# Buck.net
KiCad netlist of a schematic drawn in Altium Designer
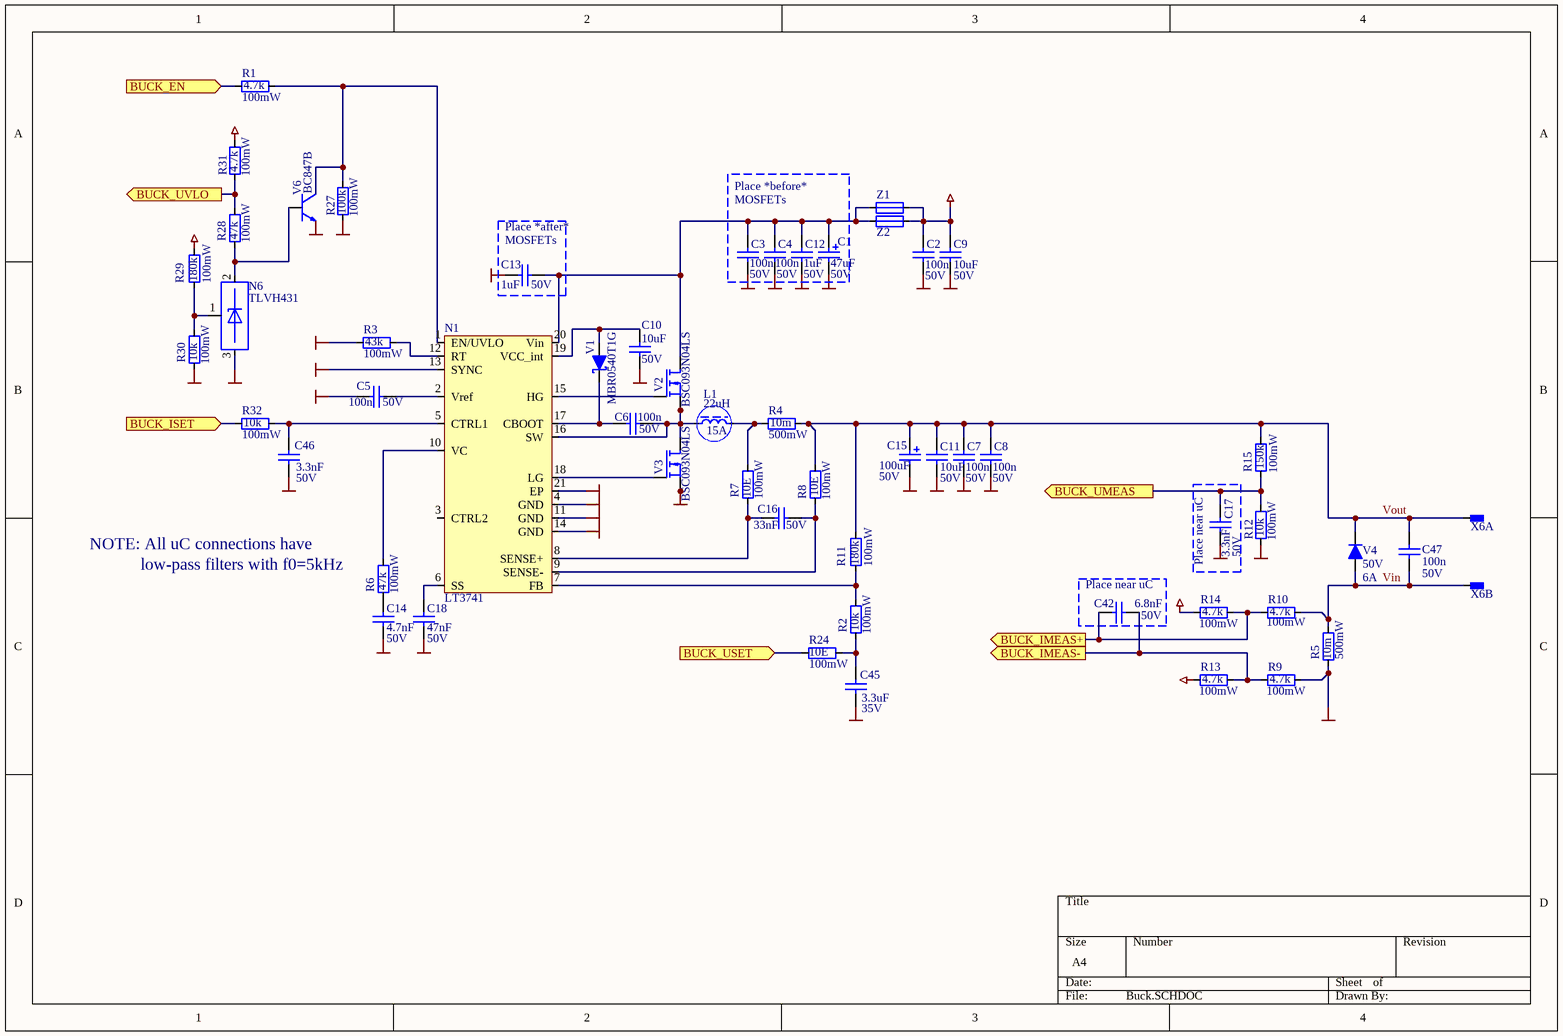
[diagram p0: Buck.SCHDOC]

(export (version "E")
  (design (tool "Eeschema 10.0.6"))
  (components
    (comp (ref "C1")
      (value "C_SMD_ALU_47U_50V_20%_PCV1H470MCL7GS")
      (footprint "SMD_CAP_CV_8x10L")
      (fields (field (name "ALTIUM_VALUE") "47uF") (field (name "VALUE2") "50V"))
      (libsource (lib "C-Capacitor") (part "C_SMD_ALU_47U_50V_20%_PCV1H470MCL7GS"))
    )
    (comp (ref "C2")
      (value "C_SMD_CER_100N_50V_10%_X7R_0603")
      (footprint "SMD_0603")
      (description "SMD Capacitor")
      (fields (field (name "ALTIUM_VALUE") "100n") (field (name "VALUE2") "50V"))
      (libsource (lib "C-Capacitor") (part "C_SMD_CER_100N_50V_10%_X7R_0603"))
    )
    (comp (ref "C3")
      (value "C_SMD_CER_100N_50V_10%_X7R_0603")
      (footprint "SMD_0603")
      (description "SMD Capacitor")
      (fields (field (name "ALTIUM_VALUE") "100n") (field (name "VALUE2") "50V"))
      (libsource (lib "C-Capacitor") (part "C_SMD_CER_100N_50V_10%_X7R_0603"))
    )
    (comp (ref "C4")
      (value "C_SMD_CER_100N_50V_10%_X7R_0603")
      (footprint "SMD_0603")
      (description "SMD Capacitor")
      (fields (field (name "ALTIUM_VALUE") "100n") (field (name "VALUE2") "50V"))
      (libsource (lib "C-Capacitor") (part "C_SMD_CER_100N_50V_10%_X7R_0603"))
    )
    (comp (ref "C5")
      (value "C_SMD_CER_100N_50V_10%_X7R_0603")
      (footprint "SMD_0603")
      (description "SMD Capacitor")
      (fields (field (name "ALTIUM_VALUE") "100n") (field (name "VALUE2") "50V"))
      (libsource (lib "C-Capacitor") (part "C_SMD_CER_100N_50V_10%_X7R_0603"))
    )
    (comp (ref "C6")
      (value "C_SMD_CER_100N_50V_10%_X7R_0603")
      (footprint "SMD_0603")
      (description "SMD Capacitor")
      (fields (field (name "ALTIUM_VALUE") "100n") (field (name "VALUE2") "50V"))
      (libsource (lib "C-Capacitor") (part "C_SMD_CER_100N_50V_10%_X7R_0603"))
    )
    (comp (ref "C7")
      (value "C_SMD_CER_100N_50V_10%_X7R_0603")
      (footprint "SMD_0603")
      (description "SMD Capacitor")
      (fields (field (name "ALTIUM_VALUE") "100n") (field (name "VALUE2") "50V"))
      (libsource (lib "C-Capacitor") (part "C_SMD_CER_100N_50V_10%_X7R_0603"))
    )
    (comp (ref "C8")
      (value "C_SMD_CER_100N_50V_10%_X7R_0603")
      (footprint "SMD_0603")
      (description "SMD Capacitor")
      (fields (field (name "ALTIUM_VALUE") "100n") (field (name "VALUE2") "50V"))
      (libsource (lib "C-Capacitor") (part "C_SMD_CER_100N_50V_10%_X7R_0603"))
    )
    (comp (ref "C9")
      (value "C_SMD_CER_10U_50V_10%_X7R_1210")
      (footprint "SMD_1210")
      (description "SMD Ceramic capacitor")
      (fields (field (name "ALTIUM_VALUE") "10uF") (field (name "VALUE2") "50V"))
      (libsource (lib "AM") (part "C_SMD_CER_10U_50V_10%_X7R_1210"))
    )
    (comp (ref "C10")
      (value "C_SMD_CER_10U_50V_10%_X7R_1210")
      (footprint "SMD_1210")
      (description "SMD Ceramic capacitor")
      (fields (field (name "ALTIUM_VALUE") "10uF") (field (name "VALUE2") "50V"))
      (libsource (lib "AM") (part "C_SMD_CER_10U_50V_10%_X7R_1210"))
    )
    (comp (ref "C11")
      (value "C_SMD_CER_10U_50V_10%_X7R_1210")
      (footprint "SMD_1210")
      (description "SMD Ceramic capacitor")
      (fields (field (name "ALTIUM_VALUE") "10uF") (field (name "VALUE2") "50V"))
      (libsource (lib "AM") (part "C_SMD_CER_10U_50V_10%_X7R_1210"))
    )
    (comp (ref "C12")
      (value "C_SMD_CER_1U_50V_10%_X7R_0805")
      (footprint "SMD_0805")
      (fields (field (name "ALTIUM_VALUE") "1uF") (field (name "VALUE2") "50V"))
      (libsource (lib "AM") (part "C_SMD_CER_1U_50V_10%_X7R_0805"))
    )
    (comp (ref "C13")
      (value "C_SMD_CER_1U_50V_10%_X7R_0805")
      (footprint "SMD_0805")
      (fields (field (name "ALTIUM_VALUE") "1uF") (field (name "VALUE2") "50V"))
      (libsource (lib "AM") (part "C_SMD_CER_1U_50V_10%_X7R_0805"))
    )
    (comp (ref "C14")
      (value "C_SMD_CER_4N7_50V_10%_X7R_0603")
      (footprint "SMD_0603")
      (description "SMD Capacitor ceramic")
      (fields (field (name "ALTIUM_VALUE") "4.7nF") (field (name "VALUE2") "50V"))
      (libsource (lib "C-Capacitor") (part "C_SMD_CER_4N7_50V_10%_X7R_0603"))
    )
    (comp (ref "C15")
      (value "C_SMD_ALU_100U_50V_20%_PCV1H101MCL2GS")
      (footprint "SMD_CAP_CV_10x12.7L")
      (fields (field (name "ALTIUM_VALUE") "100uF") (field (name "VALUE2") "50V"))
      (libsource (lib "AM") (part "C_SMD_ALU_100U_50V_20%_PCV1H101MCL2GS"))
    )
    (comp (ref "C16")
      (value "C_SMD_CER_33N_50V_10%_X7R_0603")
      (footprint "SMD_0603")
      (fields (field (name "ALTIUM_VALUE") "33nF") (field (name "VALUE2") "50V"))
      (libsource (lib "AM") (part "C_SMD_CER_33N_50V_10%_X7R_0603"))
    )
    (comp (ref "C17")
      (value "C_SMD_CER_3N3_50V_10%_X7R_0603")
      (footprint "SMD_0603")
      (description "Thinfilm Ceramic Capacitor")
      (fields (field (name "ALTIUM_VALUE") "3.3nF") (field (name "VALUE2") "50V"))
      (libsource (lib "AM") (part "C_SMD_CER_3N3_50V_10%_X7R_0603"))
    )
    (comp (ref "C18")
      (value "C_SMD_CER_47N_50V_10%_X7R_0603")
      (footprint "SMD_0603")
      (description "SMD capacitor")
      (fields (field (name "ALTIUM_VALUE") "47nF") (field (name "VALUE2") "50V"))
      (libsource (lib "C-Capacitor") (part "C_SMD_CER_47N_50V_10%_X7R_0603"))
    )
    (comp (ref "C42")
      (value "C_SMD_CER_6N8_50V_10%_X7R_0603")
      (footprint "SMD_0603")
      (fields (field (name "ALTIUM_VALUE") "6.8nF") (field (name "VALUE2") "50V"))
      (libsource (lib "AM") (part "C_SMD_CER_6N8_50V_10%_X7R_0603"))
    )
    (comp (ref "C45")
      (value "C_SMD_CER_3U3_35V_10%_X7R_0805")
      (footprint "SMD_0805")
      (fields (field (name "ALTIUM_VALUE") "3.3uF") (field (name "VALUE2") "35V"))
      (libsource (lib "AM") (part "C_SMD_CER_3U3_35V_10%_X7R_0805"))
    )
    (comp (ref "C46")
      (value "C_SMD_CER_3N3_50V_10%_X7R_0603")
      (footprint "SMD_0603")
      (description "Thinfilm Ceramic Capacitor")
      (fields (field (name "ALTIUM_VALUE") "3.3nF") (field (name "VALUE2") "50V"))
      (libsource (lib "AM") (part "C_SMD_CER_3N3_50V_10%_X7R_0603"))
    )
    (comp (ref "C47")
      (value "C_SMD_CER_100N_50V_10%_X7R_0603")
      (footprint "SMD_0603")
      (description "SMD Capacitor")
      (fields (field (name "ALTIUM_VALUE") "100n") (field (name "VALUE2") "50V"))
      (libsource (lib "C-Capacitor") (part "C_SMD_CER_100N_50V_10%_X7R_0603"))
    )
    (comp (ref "L1")
      (value "L_SMD_22U_15A_7MOHM_20%_74435582200")
      (footprint "SMD_INDUCT-74435582200")
      (fields (field (name "ALTIUM_VALUE") "22uH") (field (name "VALUE2") "15A"))
      (libsource (lib "AM") (part "L_SMD_22U_15A_7MOHM_20%_74435582200"))
    )
    (comp (ref "N1")
      (value "N_LT3741EUF_QFN-20")
      (footprint "SMD_QFN-20")
      (description "High Power, CCVC, Step-Down Controller")
      (fields (field (name "TYPE") "LT3741"))
      (libsource (lib "N-Analog") (part "N_LT3741EUF_QFN-20"))
    )
    (comp (ref "N6")
      (value "N_TLVH431_SOT23-3")
      (footprint "SMD_SOT_23_3")
      (description "LOW-VOLTAGE ADJUSTABLE PRECISION SHUNT REGULATORS")
      (fields (field (name "TYPE") "TLVH431"))
      (libsource (lib "AM") (part "N_TLVH431_SOT23-3"))
    )
    (comp (ref "R1")
      (value "R_SMD_THINFILM_4K7_0W1_1%_50PPM_0603")
      (footprint "SMD_0603")
      (description "SMD Resistor")
      (fields (field (name "ALTIUM_VALUE") "4.7k") (field (name "VALUE2") "100mW"))
      (libsource (lib "R-Resistor") (part "R_SMD_THINFILM_4K7_0W1_1%_50PPM_0603"))
    )
    (comp (ref "R2")
      (value "R_SMD_THINFILM_10K_0W1_1%_50PPM_0603")
      (footprint "SMD_0603")
      (description "SMD Resistor")
      (fields (field (name "ALTIUM_VALUE") "10k") (field (name "VALUE2") "100mW"))
      (libsource (lib "R-Resistor") (part "R_SMD_THINFILM_10K_0W1_1%_50PPM_0603"))
    )
    (comp (ref "R3")
      (value "R_SMD_THINFILM_43K_0W1_0.1%_25PPM_0603")
      (footprint "SMD_0603")
      (description "SMD Resistor")
      (fields (field (name "ALTIUM_VALUE") "43k") (field (name "VALUE2") "100mW"))
      (libsource (lib "AM") (part "R_SMD_THINFILM_43K_0W1_0.1%_25PPM_0603"))
    )
    (comp (ref "R4")
      (value "R_SMD_THICKFILM_0E01_0W5_0.5%_50PPM_1206")
      (footprint "SMD_1206")
      (description "SMD Current sense resistor")
      (fields (field (name "ALTIUM_VALUE") "10m") (field (name "VALUE2") "500mW"))
      (libsource (lib "AM") (part "R_SMD_THICKFILM_0E01_0W5_0.5%_50PPM_1206"))
    )
    (comp (ref "R5")
      (value "R_SMD_THICKFILM_0E01_0W5_0.5%_50PPM_1206")
      (footprint "SMD_1206")
      (description "SMD Current sense resistor")
      (fields (field (name "ALTIUM_VALUE") "10m") (field (name "VALUE2") "500mW"))
      (libsource (lib "AM") (part "R_SMD_THICKFILM_0E01_0W5_0.5%_50PPM_1206"))
    )
    (comp (ref "R6")
      (value "R_SMD_THINFILM_47K_0W1_1%_50PPM_0603")
      (footprint "SMD_0603")
      (description "SMD Resistor")
      (fields (field (name "ALTIUM_VALUE") "47k") (field (name "VALUE2") "100mW"))
      (libsource (lib "R-Resistor") (part "R_SMD_THINFILM_47K_0W1_1%_50PPM_0603"))
    )
    (comp (ref "R7")
      (value "R_SMD_THINFILM_10E_0W1_1%_50PPM_0603")
      (footprint "SMD_0603")
      (description "SMD Resistor")
      (fields (field (name "ALTIUM_VALUE") "10E") (field (name "VALUE2") "100mW"))
      (libsource (lib "R-Resistor") (part "R_SMD_THINFILM_10E_0W1_1%_50PPM_0603"))
    )
    (comp (ref "R8")
      (value "R_SMD_THINFILM_10E_0W1_1%_50PPM_0603")
      (footprint "SMD_0603")
      (description "SMD Resistor")
      (fields (field (name "ALTIUM_VALUE") "10E") (field (name "VALUE2") "100mW"))
      (libsource (lib "R-Resistor") (part "R_SMD_THINFILM_10E_0W1_1%_50PPM_0603"))
    )
    (comp (ref "R9")
      (value "R_SMD_THINFILM_4K7_0W1_1%_50PPM_0603")
      (footprint "SMD_0603")
      (description "SMD Resistor")
      (fields (field (name "ALTIUM_VALUE") "4.7k") (field (name "VALUE2") "100mW"))
      (libsource (lib "R-Resistor") (part "R_SMD_THINFILM_4K7_0W1_1%_50PPM_0603"))
    )
    (comp (ref "R10")
      (value "R_SMD_THINFILM_4K7_0W1_1%_50PPM_0603")
      (footprint "SMD_0603")
      (description "SMD Resistor")
      (fields (field (name "ALTIUM_VALUE") "4.7k") (field (name "VALUE2") "100mW"))
      (libsource (lib "R-Resistor") (part "R_SMD_THINFILM_4K7_0W1_1%_50PPM_0603"))
    )
    (comp (ref "R11")
      (value "R_SMD_THINFILM_180K_0W1_0.1%_25PPM_0603")
      (footprint "SMD_0603")
      (description "SMD Resistor")
      (fields (field (name "ALTIUM_VALUE") "180k") (field (name "VALUE2") "100mW"))
      (libsource (lib "AM") (part "R_SMD_THINFILM_180K_0W1_0.1%_25PPM_0603"))
    )
    (comp (ref "R12")
      (value "R_SMD_THINFILM_10K_0W1_1%_50PPM_0603")
      (footprint "SMD_0603")
      (description "SMD Resistor")
      (fields (field (name "ALTIUM_VALUE") "10k") (field (name "VALUE2") "100mW"))
      (libsource (lib "R-Resistor") (part "R_SMD_THINFILM_10K_0W1_1%_50PPM_0603"))
    )
    (comp (ref "R13")
      (value "R_SMD_THINFILM_4K7_0W1_1%_50PPM_0603")
      (footprint "SMD_0603")
      (description "SMD Resistor")
      (fields (field (name "ALTIUM_VALUE") "4.7k") (field (name "VALUE2") "100mW"))
      (libsource (lib "R-Resistor") (part "R_SMD_THINFILM_4K7_0W1_1%_50PPM_0603"))
    )
    (comp (ref "R14")
      (value "R_SMD_THINFILM_4K7_0W1_1%_50PPM_0603")
      (footprint "SMD_0603")
      (description "SMD Resistor")
      (fields (field (name "ALTIUM_VALUE") "4.7k") (field (name "VALUE2") "100mW"))
      (libsource (lib "R-Resistor") (part "R_SMD_THINFILM_4K7_0W1_1%_50PPM_0603"))
    )
    (comp (ref "R15")
      (value "R_SMD_THINFILM_150K_0W1_1%_50PPM_0603")
      (footprint "SMD_0603")
      (description "SMD Resistor")
      (fields (field (name "ALTIUM_VALUE") "150k") (field (name "VALUE2") "100mW"))
      (libsource (lib "R-Resistor") (part "R_SMD_THINFILM_150K_0W1_1%_50PPM_0603"))
    )
    (comp (ref "R24")
      (value "R_SMD_THINFILM_10E_0W1_1%_50PPM_0603")
      (footprint "SMD_0603")
      (description "SMD Resistor")
      (fields (field (name "ALTIUM_VALUE") "10E") (field (name "VALUE2") "100mW"))
      (libsource (lib "R-Resistor") (part "R_SMD_THINFILM_10E_0W1_1%_50PPM_0603"))
    )
    (comp (ref "R27")
      (value "R_SMD_THINFILM_100K_0W1_1%_50PPM_0603")
      (footprint "SMD_0603")
      (description "SMD Resistor")
      (fields (field (name "ALTIUM_VALUE") "100k") (field (name "VALUE2") "100mW"))
      (libsource (lib "R-Resistor") (part "R_SMD_THINFILM_100K_0W1_1%_50PPM_0603"))
    )
    (comp (ref "R28")
      (value "R_SMD_THINFILM_47K_0W1_1%_50PPM_0603")
      (footprint "SMD_0603")
      (description "SMD Resistor")
      (fields (field (name "ALTIUM_VALUE") "47k") (field (name "VALUE2") "100mW"))
      (libsource (lib "R-Resistor") (part "R_SMD_THINFILM_47K_0W1_1%_50PPM_0603"))
    )
    (comp (ref "R29")
      (value "R_SMD_THINFILM_180K_0W1_0.1%_25PPM_0603")
      (footprint "SMD_0603")
      (description "SMD Resistor")
      (fields (field (name "ALTIUM_VALUE") "180k") (field (name "VALUE2") "100mW"))
      (libsource (lib "AM") (part "R_SMD_THINFILM_180K_0W1_0.1%_25PPM_0603"))
    )
    (comp (ref "R30")
      (value "R_SMD_THINFILM_10K_0W1_1%_50PPM_0603")
      (footprint "SMD_0603")
      (description "SMD Resistor")
      (fields (field (name "ALTIUM_VALUE") "10k") (field (name "VALUE2") "100mW"))
      (libsource (lib "R-Resistor") (part "R_SMD_THINFILM_10K_0W1_1%_50PPM_0603"))
    )
    (comp (ref "R31")
      (value "R_SMD_THINFILM_4K7_0W1_1%_50PPM_0603")
      (footprint "SMD_0603")
      (description "SMD Resistor")
      (fields (field (name "ALTIUM_VALUE") "4.7k") (field (name "VALUE2") "100mW"))
      (libsource (lib "R-Resistor") (part "R_SMD_THINFILM_4K7_0W1_1%_50PPM_0603"))
    )
    (comp (ref "R32")
      (value "R_SMD_THINFILM_10K_0W1_1%_50PPM_0603")
      (footprint "SMD_0603")
      (description "SMD Resistor")
      (fields (field (name "ALTIUM_VALUE") "10k") (field (name "VALUE2") "100mW"))
      (libsource (lib "R-Resistor") (part "R_SMD_THINFILM_10K_0W1_1%_50PPM_0603"))
    )
    (comp (ref "V1")
      (value "V_SMD_SCHOTTKY_MBR0540T1G_40V_0A5_SOD-123")
      (footprint "SMD_SOD_123")
      (description "Schottky diode, 40V, 500mA, SOD-123")
      (fields (field (name "TYPE") "MBR0540T1G"))
      (libsource (lib "AM") (part "V_SMD_SCHOTTKY_MBR0540T1G_40V_0A5_SOD-123"))
    )
    (comp (ref "V2")
      (value "V_SMD_FET_NMOS_BSC093N04LS_40V_13A_24NC_0E0093_PG-TDSON-8")
      (footprint "SMD_PG-TDSON-8")
      (description "Fast switching mosfet for SMPS")
      (fields (field (name "TYPE") "BSC093N04LS"))
      (libsource (lib "V-Semiconductors") (part "V_SMD_FET_NMOS_BSC093N04LS_40V_13A_24NC_0E0093_PG-TDSON-8"))
    )
    (comp (ref "V3")
      (value "V_SMD_FET_NMOS_BSC093N04LS_40V_13A_24NC_0E0093_PG-TDSON-8")
      (footprint "SMD_PG-TDSON-8")
      (description "Fast switching mosfet for SMPS")
      (fields (field (name "TYPE") "BSC093N04LS"))
      (libsource (lib "V-Semiconductors") (part "V_SMD_FET_NMOS_BSC093N04LS_40V_13A_24NC_0E0093_PG-TDSON-8"))
    )
    (comp (ref "V4")
      (value "V_THT_DIODE_6A05-T_50V_6A")
      (footprint "THT_6A05-T_2")
      (description "6A05-T")
      (fields (field (name "ALTIUM_VALUE") "50V") (field (name "VALUE2") "6A"))
      (libsource (lib "V-Semiconductors") (part "V_THT_DIODE_6A05-T_50V_6A"))
    )
    (comp (ref "V6")
      (value "V_SMD_TRANS_NPN_BC847B_50V_0A2_SOT-23-3")
      (footprint "SMD_SOT_23_3")
      (description "NPN Transistor")
      (fields (field (name "TYPE") "BC847B"))
      (libsource (lib "V-Semiconductors") (part "V_SMD_TRANS_NPN_BC847B_50V_0A2_SOT-23-3"))
    )
    (comp (ref "X6")
      (value "X_CONNECTOR_P2.54_D0.9_1X2")
      (footprint "THT_CON_P2.54_D0.9_1X2")
      (description "Pitch 2.54, Diameter 0.9mm, 1 row, 2 columns")
      (libsource (lib "AM") (part "X_CONNECTOR_P2.54_D0.9_1X2"))
    )
    (comp (ref "Z1")
      (value "Z_SMD_FERRITE_5A_60E@100MHZ_0805")
      (footprint "SMD_0805")
      (description "BEAD FERRITE 60 OHM 5A")
      (libsource (lib "AM") (part "Z_SMD_FERRITE_5A_60E@100MHZ_0805"))
    )
    (comp (ref "Z2")
      (value "Z_SMD_FERRITE_5A_60E@100MHZ_0805")
      (footprint "SMD_0805")
      (description "BEAD FERRITE 60 OHM 5A")
      (libsource (lib "AM") (part "Z_SMD_FERRITE_5A_60E@100MHZ_0805"))
    )
  )
  (nets
    (net (code "1") (name "+3.3V") (class "Default")
      (node (ref "R13") (pin "2") (pinfunction "2_2") (pintype "passive"))
      (node (ref "R14") (pin "2") (pinfunction "2_2") (pintype "passive"))
      (node (ref "R31") (pin "2") (pinfunction "2_2") (pintype "passive"))
    )
    (net (code "2") (name "+36V") (class "Default")
      (node (ref "C2") (pin "2") (pinfunction "2_2") (pintype "passive"))
      (node (ref "C9") (pin "2") (pinfunction "2_2") (pintype "passive"))
      (node (ref "R29") (pin "2") (pinfunction "2_2") (pintype "passive"))
      (node (ref "Z1") (pin "2") (pinfunction "2_2") (pintype "passive"))
      (node (ref "Z2") (pin "2") (pinfunction "2_2") (pintype "passive"))
    )
    (net (code "3") (name "/BUCK_EN") (class "Default")
      (node (ref "R1") (pin "1") (pinfunction "1_1") (pintype "passive"))
    )
    (net (code "4") (name "/BUCK_IMEAS+") (class "Default")
      (node (ref "C42") (pin "1") (pinfunction "1_1") (pintype "passive"))
      (node (ref "R10") (pin "2") (pinfunction "2_2") (pintype "passive"))
      (node (ref "R14") (pin "1") (pinfunction "1_1") (pintype "passive"))
    )
    (net (code "5") (name "/BUCK_IMEAS-") (class "Default")
      (node (ref "C42") (pin "2") (pinfunction "2_2") (pintype "passive"))
      (node (ref "R13") (pin "1") (pinfunction "1_1") (pintype "passive"))
      (node (ref "R9") (pin "2") (pinfunction "2_2") (pintype "passive"))
    )
    (net (code "6") (name "/BUCK_ISET") (class "Default")
      (node (ref "R32") (pin "1") (pinfunction "1_1") (pintype "passive"))
    )
    (net (code "7") (name "/BUCK_UMEAS") (class "Default")
      (node (ref "C17") (pin "2") (pinfunction "2_2") (pintype "passive"))
      (node (ref "R12") (pin "2") (pinfunction "2_2") (pintype "passive"))
      (node (ref "R15") (pin "1") (pinfunction "1_1") (pintype "passive"))
    )
    (net (code "8") (name "/BUCK_USET") (class "Default")
      (node (ref "R24") (pin "1") (pinfunction "1_1") (pintype "passive"))
    )
    (net (code "9") (name "/BUCK_UVLO") (class "Default")
      (node (ref "R28") (pin "2") (pinfunction "2_2") (pintype "passive"))
      (node (ref "R31") (pin "1") (pinfunction "1_1") (pintype "passive"))
    )
    (net (code "10") (name "/Vin") (class "Default")
      (node (ref "C47") (pin "1") (pinfunction "1_1") (pintype "passive"))
      (node (ref "R10") (pin "1") (pinfunction "1_1") (pintype "passive"))
      (node (ref "R5") (pin "2") (pinfunction "2_2") (pintype "passive"))
      (node (ref "V4") (pin "1") (pinfunction "1_1") (pintype "passive"))
      (node (ref "X6") (pin "2") (pinfunction "2_2") (pintype "passive"))
    )
    (net (code "11") (name "/Vout") (class "Default")
      (node (ref "C11") (pin "2") (pinfunction "2_2") (pintype "passive"))
      (node (ref "C15") (pin "2") (pinfunction "2_2") (pintype "passive"))
      (node (ref "C47") (pin "2") (pinfunction "2_2") (pintype "passive"))
      (node (ref "C7") (pin "2") (pinfunction "2_2") (pintype "passive"))
      (node (ref "C8") (pin "2") (pinfunction "2_2") (pintype "passive"))
      (node (ref "R11") (pin "2") (pinfunction "2_2") (pintype "passive"))
      (node (ref "R15") (pin "2") (pinfunction "2_2") (pintype "passive"))
      (node (ref "R4") (pin "2") (pinfunction "2_2") (pintype "passive"))
      (node (ref "R8") (pin "2") (pinfunction "2_2") (pintype "passive"))
      (node (ref "V4") (pin "2") (pinfunction "2_2") (pintype "passive"))
      (node (ref "X6") (pin "1") (pinfunction "1_1") (pintype "passive"))
    )
    (net (code "12") (name "GND") (class "Default")
      (node (ref "C1") (pin "1") (pinfunction "1_1") (pintype "passive"))
      (node (ref "C10") (pin "2") (pinfunction "2_2") (pintype "passive"))
      (node (ref "C11") (pin "1") (pinfunction "1_1") (pintype "passive"))
      (node (ref "C12") (pin "1") (pinfunction "1_1") (pintype "passive"))
      (node (ref "C13") (pin "2") (pinfunction "2_2") (pintype "passive"))
      (node (ref "C14") (pin "1") (pinfunction "1_1") (pintype "passive"))
      (node (ref "C15") (pin "1") (pinfunction "1_1") (pintype "passive"))
      (node (ref "C17") (pin "1") (pinfunction "1_1") (pintype "passive"))
      (node (ref "C18") (pin "1") (pinfunction "1_1") (pintype "passive"))
      (node (ref "C2") (pin "1") (pinfunction "1_1") (pintype "passive"))
      (node (ref "C3") (pin "1") (pinfunction "1_1") (pintype "passive"))
      (node (ref "C4") (pin "1") (pinfunction "1_1") (pintype "passive"))
      (node (ref "C45") (pin "1") (pinfunction "1_1") (pintype "passive"))
      (node (ref "C46") (pin "1") (pinfunction "1_1") (pintype "passive"))
      (node (ref "C5") (pin "2") (pinfunction "2_2") (pintype "passive"))
      (node (ref "C7") (pin "1") (pinfunction "1_1") (pintype "passive"))
      (node (ref "C8") (pin "1") (pinfunction "1_1") (pintype "passive"))
      (node (ref "C9") (pin "1") (pinfunction "1_1") (pintype "passive"))
      (node (ref "N1") (pin "11") (pinfunction "GND_11") (pintype "passive"))
      (node (ref "N1") (pin "13") (pinfunction "SYNC_13") (pintype "passive"))
      (node (ref "N1") (pin "14") (pinfunction "GND_14") (pintype "passive"))
      (node (ref "N1") (pin "21") (pinfunction "EP_21") (pintype "passive"))
      (node (ref "N1") (pin "4") (pinfunction "GND_4") (pintype "passive"))
      (node (ref "N6") (pin "3") (pinfunction "3_3") (pintype "passive"))
      (node (ref "R12") (pin "1") (pinfunction "1_1") (pintype "passive"))
      (node (ref "R27") (pin "1") (pinfunction "1_1") (pintype "passive"))
      (node (ref "R3") (pin "1") (pinfunction "1_1") (pintype "passive"))
      (node (ref "R30") (pin "1") (pinfunction "1_1") (pintype "passive"))
      (node (ref "R5") (pin "1") (pinfunction "1_1") (pintype "passive"))
      (node (ref "R9") (pin "1") (pinfunction "1_1") (pintype "passive"))
      (node (ref "V3") (pin "1") (pinfunction "Source1_1") (pintype "passive"))
      (node (ref "V3") (pin "2") (pinfunction "Source2_2") (pintype "passive"))
      (node (ref "V3") (pin "3") (pinfunction "Source3_3") (pintype "passive"))
      (node (ref "V6") (pin "2") (pinfunction "E_2") (pintype "passive"))
    )
    (net (code "13") (name "Net-(C14-Pad2)") (class "Default")
      (node (ref "C14") (pin "2") (pinfunction "2_2") (pintype "passive"))
      (node (ref "R6") (pin "1") (pinfunction "1_1") (pintype "passive"))
    )
    (net (code "14") (name "Net-(C45-Pad2)") (class "Default")
      (node (ref "C45") (pin "2") (pinfunction "2_2") (pintype "passive"))
      (node (ref "R2") (pin "2") (pinfunction "2_2") (pintype "passive"))
      (node (ref "R24") (pin "2") (pinfunction "2_2") (pintype "passive"))
    )
    (net (code "15") (name "Net-(L1-Pad2)") (class "Default")
      (node (ref "L1") (pin "2") (pinfunction "2_2") (pintype "passive"))
      (node (ref "R4") (pin "1") (pinfunction "1_1") (pintype "passive"))
      (node (ref "R7") (pin "2") (pinfunction "2_2") (pintype "passive"))
    )
    (net (code "16") (name "Net-(N1-CBOOT)") (class "Default")
      (node (ref "C6") (pin "1") (pinfunction "1_1") (pintype "passive"))
      (node (ref "N1") (pin "17") (pinfunction "CBOOT_17") (pintype "passive"))
      (node (ref "V1") (pin "2") (pinfunction "2_2") (pintype "passive"))
    )
    (net (code "17") (name "Net-(N1-CTRL1)") (class "Default")
      (node (ref "C46") (pin "2") (pinfunction "2_2") (pintype "passive"))
      (node (ref "N1") (pin "5") (pinfunction "CTRL1_5") (pintype "passive"))
      (node (ref "R32") (pin "2") (pinfunction "2_2") (pintype "passive"))
    )
    (net (code "18") (name "Net-(N1-EN{slash}UVLO)") (class "Default")
      (node (ref "N1") (pin "1") (pinfunction "EN/UVLO_1") (pintype "passive"))
      (node (ref "R1") (pin "2") (pinfunction "2_2") (pintype "passive"))
      (node (ref "R27") (pin "2") (pinfunction "2_2") (pintype "passive"))
      (node (ref "V6") (pin "3") (pinfunction "C_3") (pintype "passive"))
    )
    (net (code "19") (name "Net-(N1-FB)") (class "Default")
      (node (ref "N1") (pin "7") (pinfunction "FB_7") (pintype "passive"))
      (node (ref "R11") (pin "1") (pinfunction "1_1") (pintype "passive"))
      (node (ref "R2") (pin "1") (pinfunction "1_1") (pintype "passive"))
    )
    (net (code "20") (name "Net-(N1-HG)") (class "Default")
      (node (ref "N1") (pin "15") (pinfunction "HG_15") (pintype "passive"))
      (node (ref "V2") (pin "4") (pinfunction "Gate_4") (pintype "passive"))
    )
    (net (code "21") (name "Net-(N1-LG)") (class "Default")
      (node (ref "N1") (pin "18") (pinfunction "LG_18") (pintype "passive"))
      (node (ref "V3") (pin "4") (pinfunction "Gate_4") (pintype "passive"))
    )
    (net (code "22") (name "Net-(N1-RT)") (class "Default")
      (node (ref "N1") (pin "12") (pinfunction "RT_12") (pintype "passive"))
      (node (ref "R3") (pin "2") (pinfunction "2_2") (pintype "passive"))
    )
    (net (code "23") (name "Net-(N1-SENSE+)") (class "Default")
      (node (ref "C16") (pin "2") (pinfunction "2_2") (pintype "passive"))
      (node (ref "N1") (pin "8") (pinfunction "SENSE+_8") (pintype "passive"))
      (node (ref "R7") (pin "1") (pinfunction "1_1") (pintype "passive"))
    )
    (net (code "24") (name "Net-(N1-SENSE-)") (class "Default")
      (node (ref "C16") (pin "1") (pinfunction "1_1") (pintype "passive"))
      (node (ref "N1") (pin "9") (pinfunction "SENSE-_9") (pintype "passive"))
      (node (ref "R8") (pin "1") (pinfunction "1_1") (pintype "passive"))
    )
    (net (code "25") (name "Net-(N1-SS)") (class "Default")
      (node (ref "C18") (pin "2") (pinfunction "2_2") (pintype "passive"))
      (node (ref "N1") (pin "6") (pinfunction "SS_6") (pintype "passive"))
    )
    (net (code "26") (name "Net-(N1-SW)") (class "Default")
      (node (ref "C6") (pin "2") (pinfunction "2_2") (pintype "passive"))
      (node (ref "L1") (pin "1") (pinfunction "1_1") (pintype "passive"))
      (node (ref "N1") (pin "16") (pinfunction "SW_16") (pintype "passive"))
      (node (ref "V2") (pin "1") (pinfunction "Source1_1") (pintype "passive"))
      (node (ref "V2") (pin "2") (pinfunction "Source2_2") (pintype "passive"))
      (node (ref "V2") (pin "3") (pinfunction "Source3_3") (pintype "passive"))
      (node (ref "V3") (pin "5") (pinfunction "Drain_5") (pintype "passive"))
    )
    (net (code "27") (name "Net-(N1-VC)") (class "Default")
      (node (ref "N1") (pin "10") (pinfunction "VC_10") (pintype "passive"))
      (node (ref "R6") (pin "2") (pinfunction "2_2") (pintype "passive"))
    )
    (net (code "28") (name "Net-(N1-VCC_int)") (class "Default")
      (node (ref "C10") (pin "1") (pinfunction "1_1") (pintype "passive"))
      (node (ref "N1") (pin "19") (pinfunction "VCC_int_19") (pintype "passive"))
      (node (ref "V1") (pin "1") (pinfunction "1_1") (pintype "passive"))
    )
    (net (code "29") (name "Net-(N1-Vin)") (class "Default")
      (node (ref "C1") (pin "2") (pinfunction "2_2") (pintype "passive"))
      (node (ref "C12") (pin "2") (pinfunction "2_2") (pintype "passive"))
      (node (ref "C13") (pin "1") (pinfunction "1_1") (pintype "passive"))
      (node (ref "C3") (pin "2") (pinfunction "2_2") (pintype "passive"))
      (node (ref "C4") (pin "2") (pinfunction "2_2") (pintype "passive"))
      (node (ref "N1") (pin "20") (pinfunction "Vin_20") (pintype "passive"))
      (node (ref "V2") (pin "5") (pinfunction "Drain_5") (pintype "passive"))
      (node (ref "Z1") (pin "1") (pinfunction "1_1") (pintype "passive"))
      (node (ref "Z2") (pin "1") (pinfunction "1_1") (pintype "passive"))
    )
    (net (code "30") (name "Net-(N1-Vref)") (class "Default")
      (node (ref "C5") (pin "1") (pinfunction "1_1") (pintype "passive"))
      (node (ref "N1") (pin "2") (pinfunction "Vref_2") (pintype "passive"))
    )
    (net (code "31") (name "Net-(N6-Pad1)") (class "Default")
      (node (ref "N6") (pin "1") (pinfunction "1_1") (pintype "passive"))
      (node (ref "R29") (pin "1") (pinfunction "1_1") (pintype "passive"))
      (node (ref "R30") (pin "2") (pinfunction "2_2") (pintype "passive"))
    )
    (net (code "32") (name "Net-(V6-B)") (class "Default")
      (node (ref "N6") (pin "2") (pinfunction "2_2") (pintype "passive"))
      (node (ref "R28") (pin "1") (pinfunction "1_1") (pintype "passive"))
      (node (ref "V6") (pin "1") (pinfunction "B_1") (pintype "passive"))
    )
    (net (code "33") (name "unconnected-(N1-CTRL2-Pad3)") (class "Default")
      (node (ref "N1") (pin "3") (pinfunction "CTRL2_3") (pintype "passive"))
    )
  )
)
